# ADC_DSP.net
KiCad netlist of a schematic drawn in EAGLE
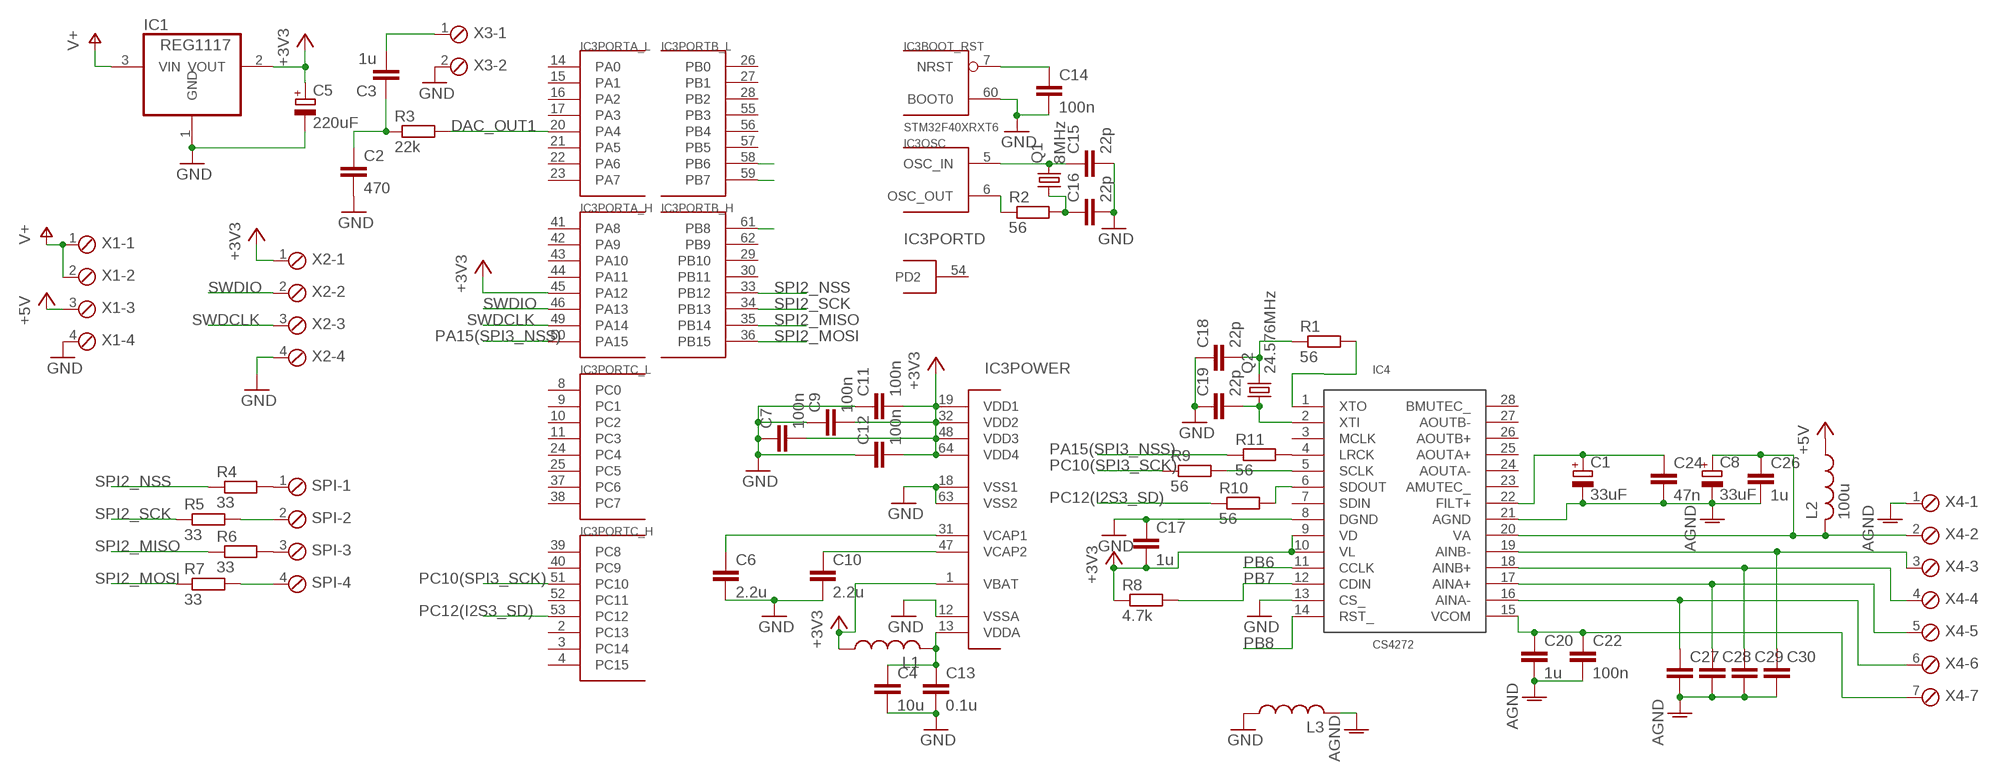
[diagram p0: schematic, sheet 1]

(export (version "E")
  (design (tool "Eeschema 10.0.6"))
  (components
    (comp (ref "C1")
      (value "33uF")
      (footprint "eagle-import:153CLV-0605")
      (libsource (lib "eagle-import") (part "CPOL-EU153CLV-0605"))
    )
    (comp (ref "C2")
      (value "470")
      (footprint "eagle-import:C0603")
      (libsource (lib "eagle-import") (part "C-EUC0603"))
    )
    (comp (ref "C3")
      (value "1u")
      (footprint "eagle-import:C0603")
      (libsource (lib "eagle-import") (part "C-EUC0603"))
    )
    (comp (ref "C4")
      (value "10u")
      (footprint "eagle-import:C0805")
      (libsource (lib "eagle-import") (part "C-EUC0805"))
    )
    (comp (ref "C5")
      (value "220uF")
      (footprint "eagle-import:153CLV-0605")
      (libsource (lib "eagle-import") (part "CPOL-EU153CLV-0605"))
    )
    (comp (ref "C6")
      (value "2.2u")
      (footprint "eagle-import:C0603")
      (libsource (lib "eagle-import") (part "C-EUC0603"))
    )
    (comp (ref "C7")
      (value "100n")
      (footprint "eagle-import:C0603")
      (libsource (lib "eagle-import") (part "C-EUC0603"))
    )
    (comp (ref "C8")
      (value "33uF")
      (footprint "eagle-import:153CLV-0605")
      (libsource (lib "eagle-import") (part "CPOL-EU153CLV-0605"))
    )
    (comp (ref "C9")
      (value "100n")
      (footprint "eagle-import:C0603")
      (libsource (lib "eagle-import") (part "C-EUC0603"))
    )
    (comp (ref "C10")
      (value "2.2u")
      (footprint "eagle-import:C0603")
      (libsource (lib "eagle-import") (part "C-EUC0603"))
    )
    (comp (ref "C11")
      (value "100n")
      (footprint "eagle-import:C0603")
      (libsource (lib "eagle-import") (part "C-EUC0603"))
    )
    (comp (ref "C12")
      (value "100n")
      (footprint "eagle-import:C0603")
      (libsource (lib "eagle-import") (part "C-EUC0603"))
    )
    (comp (ref "C13")
      (value "0.1u")
      (footprint "eagle-import:C0603")
      (libsource (lib "eagle-import") (part "C-EUC0603"))
    )
    (comp (ref "C14")
      (value "100n")
      (footprint "eagle-import:C0603")
      (libsource (lib "eagle-import") (part "C-EUC0603"))
    )
    (comp (ref "C15")
      (value "22p")
      (footprint "eagle-import:C0603")
      (libsource (lib "eagle-import") (part "C-EUC0603"))
    )
    (comp (ref "C16")
      (value "22p")
      (footprint "eagle-import:C0603")
      (libsource (lib "eagle-import") (part "C-EUC0603"))
    )
    (comp (ref "C17")
      (value "1u")
      (footprint "eagle-import:C0603")
      (libsource (lib "eagle-import") (part "C-EUC0603"))
    )
    (comp (ref "C18")
      (value "22p")
      (footprint "eagle-import:C0603")
      (libsource (lib "eagle-import") (part "C-EUC0603"))
    )
    (comp (ref "C19")
      (value "22p")
      (footprint "eagle-import:C0603")
      (libsource (lib "eagle-import") (part "C-EUC0603"))
    )
    (comp (ref "C20")
      (value "1u")
      (footprint "eagle-import:C0603")
      (libsource (lib "eagle-import") (part "C-EUC0603"))
    )
    (comp (ref "C22")
      (value "100n")
      (footprint "eagle-import:C0603")
      (libsource (lib "eagle-import") (part "C-EUC0603"))
    )
    (comp (ref "C24")
      (value "47n")
      (footprint "eagle-import:C0805")
      (libsource (lib "eagle-import") (part "C-EUC0805"))
    )
    (comp (ref "C26")
      (value "1u")
      (footprint "eagle-import:C0603")
      (libsource (lib "eagle-import") (part "C-EUC0603"))
    )
    (comp (ref "C27")
      (value "C-EUC0805")
      (footprint "eagle-import:C0805")
      (libsource (lib "eagle-import") (part "C-EUC0805"))
    )
    (comp (ref "C28")
      (value "C-EUC0805")
      (footprint "eagle-import:C0805")
      (libsource (lib "eagle-import") (part "C-EUC0805"))
    )
    (comp (ref "C29")
      (value "C-EUC0805")
      (footprint "eagle-import:C0805")
      (libsource (lib "eagle-import") (part "C-EUC0805"))
    )
    (comp (ref "C30")
      (value "C-EUC0805")
      (footprint "eagle-import:C0805")
      (libsource (lib "eagle-import") (part "C-EUC0805"))
    )
    (comp (ref "IC1")
      (value "REG1117")
      (footprint "eagle-import:SOT223")
      (libsource (lib "eagle-import") (part "REG1117"))
    )
    (comp (ref "IC3")
      (value "STM32F40XRXT6")
      (footprint "eagle-import:TQFP64")
      (libsource (lib "eagle-import") (part "STM32F40XRXT6"))
    )
    (comp (ref "IC4")
      (value "CS4272")
      (footprint "eagle-import:TSSOP28")
      (libsource (lib "eagle-import") (part "CS4272"))
    )
    (comp (ref "L1")
      (value "L-USL2012C")
      (footprint "eagle-import:L2012C")
      (libsource (lib "eagle-import") (part "L-USL2012C"))
    )
    (comp (ref "L2")
      (value "100u")
      (footprint "eagle-import:0207_12")
      (libsource (lib "eagle-import") (part "L-US0207/12"))
    )
    (comp (ref "L3")
      (value "L-USL2012C")
      (footprint "eagle-import:L2012C")
      (libsource (lib "eagle-import") (part "L-USL2012C"))
    )
    (comp (ref "Q1")
      (value "8MHz")
      (footprint "eagle-import:HC49_S")
      (libsource (lib "eagle-import") (part "CRYSTALHC49S"))
    )
    (comp (ref "Q2")
      (value "24.576MHz")
      (footprint "eagle-import:HC49_S")
      (libsource (lib "eagle-import") (part "CRYSTALHC49S"))
    )
    (comp (ref "R1")
      (value "56")
      (footprint "eagle-import:R0603")
      (libsource (lib "eagle-import") (part "R-EU_R0603"))
    )
    (comp (ref "R2")
      (value "56")
      (footprint "eagle-import:R0603")
      (libsource (lib "eagle-import") (part "R-EU_R0603"))
    )
    (comp (ref "R3")
      (value "22k")
      (footprint "eagle-import:R0603")
      (libsource (lib "eagle-import") (part "R-EU_R0603"))
    )
    (comp (ref "R4")
      (value "33")
      (footprint "eagle-import:R0603")
      (libsource (lib "eagle-import") (part "R-EU_R0603"))
    )
    (comp (ref "R5")
      (value "33")
      (footprint "eagle-import:R0603")
      (libsource (lib "eagle-import") (part "R-EU_R0603"))
    )
    (comp (ref "R6")
      (value "33")
      (footprint "eagle-import:R0603")
      (libsource (lib "eagle-import") (part "R-EU_R0603"))
    )
    (comp (ref "R7")
      (value "33")
      (footprint "eagle-import:R0603")
      (libsource (lib "eagle-import") (part "R-EU_R0603"))
    )
    (comp (ref "R8")
      (value "4.7k")
      (footprint "eagle-import:R0603")
      (libsource (lib "eagle-import") (part "R-EU_R0603"))
    )
    (comp (ref "R9")
      (value "56")
      (footprint "eagle-import:R0603")
      (libsource (lib "eagle-import") (part "R-EU_R0603"))
    )
    (comp (ref "R10")
      (value "56")
      (footprint "eagle-import:R0603")
      (libsource (lib "eagle-import") (part "R-EU_R0603"))
    )
    (comp (ref "R11")
      (value "56")
      (footprint "eagle-import:R0603")
      (libsource (lib "eagle-import") (part "R-EU_R0603"))
    )
    (comp (ref "SPI")
      (value "MPT4")
      (footprint "eagle-import:4POL254")
      (libsource (lib "eagle-import") (part "MPT4"))
    )
    (comp (ref "X1")
      (value "MPT4")
      (footprint "eagle-import:4POL254")
      (libsource (lib "eagle-import") (part "MPT4"))
    )
    (comp (ref "X2")
      (value "MPT4")
      (footprint "eagle-import:4POL254")
      (libsource (lib "eagle-import") (part "MPT4"))
    )
    (comp (ref "X3")
      (value "MPT2")
      (footprint "eagle-import:2POL254")
      (libsource (lib "eagle-import") (part "MPT2"))
    )
    (comp (ref "X4")
      (value "MPT7")
      (footprint "eagle-import:7POL254")
      (libsource (lib "eagle-import") (part "MPT7"))
    )
  )
  (nets
    (net (code "1") (name "+3V3") (class "Default")
      (node (ref "C11") (pin "2") (pinfunction "2_2") (pintype "passive"))
      (node (ref "C12") (pin "2") (pinfunction "2_2") (pintype "passive"))
      (node (ref "C17") (pin "2") (pinfunction "2_2") (pintype "passive"))
      (node (ref "C5") (pin "+") (pinfunction "+_+") (pintype "passive"))
      (node (ref "C7") (pin "2") (pinfunction "2_2") (pintype "passive"))
      (node (ref "C9") (pin "2") (pinfunction "2_2") (pintype "passive"))
      (node (ref "IC1") (pin "2") (pinfunction "VOUT_2") (pintype "output"))
      (node (ref "IC3") (pin "1") (pinfunction "VBAT_1") (pintype "bidirectional"))
      (node (ref "IC3") (pin "19") (pinfunction "VDD1_19") (pintype "bidirectional"))
      (node (ref "IC3") (pin "32") (pinfunction "VDD2_32") (pintype "bidirectional"))
      (node (ref "IC3") (pin "45") (pinfunction "PA12_45") (pintype "bidirectional"))
      (node (ref "IC3") (pin "48") (pinfunction "VDD3_48") (pintype "bidirectional"))
      (node (ref "IC3") (pin "64") (pinfunction "VDD4_64") (pintype "bidirectional"))
      (node (ref "IC4") (pin "10") (pinfunction "VL_10") (pintype "bidirectional"))
      (node (ref "IC4") (pin "9") (pinfunction "VD_9") (pintype "bidirectional"))
      (node (ref "L1") (pin "1") (pinfunction "1_1") (pintype "passive"))
      (node (ref "R8") (pin "1") (pinfunction "1_1") (pintype "passive"))
      (node (ref "X2") (pin "1") (pinfunction "1_1") (pintype "passive"))
    )
    (net (code "2") (name "+5V") (class "Default")
      (node (ref "L2") (pin "1") (pinfunction "1_1") (pintype "passive"))
      (node (ref "X1") (pin "3") (pinfunction "1_3") (pintype "passive"))
    )
    (net (code "3") (name "/DAC_OUT1") (class "Default")
      (node (ref "IC3") (pin "20") (pinfunction "PA4_20") (pintype "bidirectional"))
      (node (ref "R3") (pin "2") (pinfunction "2_2") (pintype "passive"))
    )
    (net (code "4") (name "/PA15(SPI3_NSS)") (class "Default")
      (node (ref "IC3") (pin "50") (pinfunction "PA15_50") (pintype "bidirectional"))
      (node (ref "R11") (pin "1") (pinfunction "1_1") (pintype "passive"))
    )
    (net (code "5") (name "/PB6") (class "Default")
      (node (ref "IC3") (pin "58") (pinfunction "PB6_58") (pintype "bidirectional"))
      (node (ref "IC4") (pin "11") (pinfunction "CCLK_11") (pintype "bidirectional"))
    )
    (net (code "6") (name "/PB7") (class "Default")
      (node (ref "IC3") (pin "59") (pinfunction "PB7_59") (pintype "bidirectional"))
      (node (ref "IC4") (pin "12") (pinfunction "CDIN_12") (pintype "bidirectional"))
      (node (ref "R8") (pin "2") (pinfunction "2_2") (pintype "passive"))
    )
    (net (code "7") (name "/PB8") (class "Default")
      (node (ref "IC3") (pin "61") (pinfunction "PB8_61") (pintype "bidirectional"))
      (node (ref "IC4") (pin "14") (pinfunction "RST__14") (pintype "bidirectional"))
    )
    (net (code "8") (name "/PC10(SPI3_SCK)") (class "Default")
      (node (ref "IC3") (pin "51") (pinfunction "PC10_51") (pintype "bidirectional"))
      (node (ref "R9") (pin "1") (pinfunction "1_1") (pintype "passive"))
    )
    (net (code "9") (name "/PC12(I2S3_SD)") (class "Default")
      (node (ref "IC3") (pin "53") (pinfunction "PC12_53") (pintype "bidirectional"))
      (node (ref "R10") (pin "1") (pinfunction "1_1") (pintype "passive"))
    )
    (net (code "10") (name "/SPI2_MISO") (class "Default")
      (node (ref "IC3") (pin "35") (pinfunction "PB14_35") (pintype "bidirectional"))
      (node (ref "R6") (pin "1") (pinfunction "1_1") (pintype "passive"))
    )
    (net (code "11") (name "/SPI2_MOSI") (class "Default")
      (node (ref "IC3") (pin "36") (pinfunction "PB15_36") (pintype "bidirectional"))
      (node (ref "R7") (pin "1") (pinfunction "1_1") (pintype "passive"))
    )
    (net (code "12") (name "/SPI2_NSS") (class "Default")
      (node (ref "IC3") (pin "33") (pinfunction "PB12_33") (pintype "bidirectional"))
      (node (ref "R4") (pin "1") (pinfunction "1_1") (pintype "passive"))
    )
    (net (code "13") (name "/SPI2_SCK") (class "Default")
      (node (ref "IC3") (pin "34") (pinfunction "PB13_34") (pintype "bidirectional"))
      (node (ref "R5") (pin "1") (pinfunction "1_1") (pintype "passive"))
    )
    (net (code "14") (name "/SWDCLK") (class "Default")
      (node (ref "IC3") (pin "49") (pinfunction "PA14_49") (pintype "bidirectional"))
      (node (ref "X2") (pin "3") (pinfunction "1_3") (pintype "passive"))
    )
    (net (code "15") (name "/SWDIO") (class "Default")
      (node (ref "IC3") (pin "46") (pinfunction "PA13_46") (pintype "bidirectional"))
      (node (ref "X2") (pin "2") (pinfunction "1_2") (pintype "passive"))
    )
    (net (code "16") (name "AGND") (class "Default")
      (node (ref "C1") (pin "-") (pinfunction "-_-") (pintype "passive"))
      (node (ref "C20") (pin "2") (pinfunction "2_2") (pintype "passive"))
      (node (ref "C22") (pin "2") (pinfunction "2_2") (pintype "passive"))
      (node (ref "C24") (pin "2") (pinfunction "2_2") (pintype "passive"))
      (node (ref "C26") (pin "2") (pinfunction "2_2") (pintype "passive"))
      (node (ref "C27") (pin "2") (pinfunction "2_2") (pintype "passive"))
      (node (ref "C28") (pin "2") (pinfunction "2_2") (pintype "passive"))
      (node (ref "C29") (pin "2") (pinfunction "2_2") (pintype "passive"))
      (node (ref "C30") (pin "2") (pinfunction "2_2") (pintype "passive"))
      (node (ref "C8") (pin "-") (pinfunction "-_-") (pintype "passive"))
      (node (ref "IC4") (pin "21") (pinfunction "AGND_21") (pintype "bidirectional"))
      (node (ref "L3") (pin "2") (pinfunction "2_2") (pintype "passive"))
      (node (ref "X4") (pin "1") (pinfunction "1_1") (pintype "passive"))
    )
    (net (code "17") (name "GND") (class "Default")
      (node (ref "C10") (pin "2") (pinfunction "2_2") (pintype "passive"))
      (node (ref "C11") (pin "1") (pinfunction "1_1") (pintype "passive"))
      (node (ref "C12") (pin "1") (pinfunction "1_1") (pintype "passive"))
      (node (ref "C13") (pin "2") (pinfunction "2_2") (pintype "passive"))
      (node (ref "C14") (pin "2") (pinfunction "2_2") (pintype "passive"))
      (node (ref "C15") (pin "2") (pinfunction "2_2") (pintype "passive"))
      (node (ref "C16") (pin "2") (pinfunction "2_2") (pintype "passive"))
      (node (ref "C17") (pin "1") (pinfunction "1_1") (pintype "passive"))
      (node (ref "C18") (pin "1") (pinfunction "1_1") (pintype "passive"))
      (node (ref "C19") (pin "1") (pinfunction "1_1") (pintype "passive"))
      (node (ref "C2") (pin "2") (pinfunction "2_2") (pintype "passive"))
      (node (ref "C4") (pin "2") (pinfunction "2_2") (pintype "passive"))
      (node (ref "C5") (pin "-") (pinfunction "-_-") (pintype "passive"))
      (node (ref "C6") (pin "2") (pinfunction "2_2") (pintype "passive"))
      (node (ref "C7") (pin "1") (pinfunction "1_1") (pintype "passive"))
      (node (ref "C9") (pin "1") (pinfunction "1_1") (pintype "passive"))
      (node (ref "IC1") (pin "1") (pinfunction "GND_1") (pintype "power_in"))
      (node (ref "IC3") (pin "12") (pinfunction "VSSA_12") (pintype "bidirectional"))
      (node (ref "IC3") (pin "18") (pinfunction "VSS1_18") (pintype "bidirectional"))
      (node (ref "IC3") (pin "60") (pinfunction "BOOT0_60") (pintype "input"))
      (node (ref "IC3") (pin "63") (pinfunction "VSS2_63") (pintype "bidirectional"))
      (node (ref "IC4") (pin "13") (pinfunction "CS__13") (pintype "bidirectional"))
      (node (ref "IC4") (pin "8") (pinfunction "DGND_8") (pintype "bidirectional"))
      (node (ref "L3") (pin "1") (pinfunction "1_1") (pintype "passive"))
      (node (ref "X1") (pin "4") (pinfunction "1_4") (pintype "passive"))
      (node (ref "X2") (pin "4") (pinfunction "1_4") (pintype "passive"))
      (node (ref "X3") (pin "2") (pinfunction "1_2") (pintype "passive"))
    )
    (net (code "18") (name "Net-(C2-Pad1)") (class "Default")
      (node (ref "C2") (pin "1") (pinfunction "1_1") (pintype "passive"))
      (node (ref "C3") (pin "1") (pinfunction "1_1") (pintype "passive"))
      (node (ref "R3") (pin "1") (pinfunction "1_1") (pintype "passive"))
    )
    (net (code "19") (name "Net-(C3-Pad2)") (class "Default")
      (node (ref "C3") (pin "2") (pinfunction "2_2") (pintype "passive"))
      (node (ref "X3") (pin "1") (pinfunction "1_1") (pintype "passive"))
    )
    (net (code "20") (name "Net-(C16-Pad1)") (class "Default")
      (node (ref "C16") (pin "1") (pinfunction "1_1") (pintype "passive"))
      (node (ref "Q1") (pin "1") (pinfunction "1_1") (pintype "passive"))
      (node (ref "R2") (pin "2") (pinfunction "2_2") (pintype "passive"))
    )
    (net (code "21") (name "Net-(C18-Pad2)") (class "Default")
      (node (ref "C18") (pin "2") (pinfunction "2_2") (pintype "passive"))
      (node (ref "Q2") (pin "2") (pinfunction "2_2") (pintype "passive"))
      (node (ref "R1") (pin "1") (pinfunction "1_1") (pintype "passive"))
    )
    (net (code "22") (name "Net-(IC3A-NRST)") (class "Default")
      (node (ref "C14") (pin "1") (pinfunction "1_1") (pintype "passive"))
      (node (ref "IC3") (pin "7") (pinfunction "NRST_7") (pintype "input"))
    )
    (net (code "23") (name "Net-(IC3B-OSC_IN)") (class "Default")
      (node (ref "C15") (pin "1") (pinfunction "1_1") (pintype "passive"))
      (node (ref "IC3") (pin "5") (pinfunction "OSC_IN_5") (pintype "input"))
      (node (ref "Q1") (pin "2") (pinfunction "2_2") (pintype "passive"))
    )
    (net (code "24") (name "Net-(IC3B-OSC_OUT)") (class "Default")
      (node (ref "IC3") (pin "6") (pinfunction "OSC_OUT_6") (pintype "output"))
      (node (ref "R2") (pin "1") (pinfunction "1_1") (pintype "passive"))
    )
    (net (code "25") (name "Net-(IC3J-VCAP1)") (class "Default")
      (node (ref "C6") (pin "1") (pinfunction "1_1") (pintype "passive"))
      (node (ref "IC3") (pin "31") (pinfunction "VCAP1_31") (pintype "bidirectional"))
    )
    (net (code "26") (name "Net-(IC3J-VCAP2)") (class "Default")
      (node (ref "C10") (pin "1") (pinfunction "1_1") (pintype "passive"))
      (node (ref "IC3") (pin "47") (pinfunction "VCAP2_47") (pintype "bidirectional"))
    )
    (net (code "27") (name "Net-(IC3J-VDDA)") (class "Default")
      (node (ref "C13") (pin "1") (pinfunction "1_1") (pintype "passive"))
      (node (ref "C4") (pin "1") (pinfunction "1_1") (pintype "passive"))
      (node (ref "IC3") (pin "13") (pinfunction "VDDA_13") (pintype "bidirectional"))
      (node (ref "L1") (pin "2") (pinfunction "2_2") (pintype "passive"))
    )
    (net (code "28") (name "Net-(IC4-AINA+)") (class "Default")
      (node (ref "C28") (pin "1") (pinfunction "1_1") (pintype "passive"))
      (node (ref "IC4") (pin "17") (pinfunction "AINA+_17") (pintype "bidirectional"))
      (node (ref "X4") (pin "5") (pinfunction "1_5") (pintype "passive"))
    )
    (net (code "29") (name "Net-(IC4-AINA-)") (class "Default")
      (node (ref "C27") (pin "1") (pinfunction "1_1") (pintype "passive"))
      (node (ref "IC4") (pin "16") (pinfunction "AINA-_16") (pintype "bidirectional"))
      (node (ref "X4") (pin "6") (pinfunction "1_6") (pintype "passive"))
    )
    (net (code "30") (name "Net-(IC4-AINB+)") (class "Default")
      (node (ref "C29") (pin "1") (pinfunction "1_1") (pintype "passive"))
      (node (ref "IC4") (pin "18") (pinfunction "AINB+_18") (pintype "bidirectional"))
      (node (ref "X4") (pin "4") (pinfunction "1_4") (pintype "passive"))
    )
    (net (code "31") (name "Net-(IC4-AINB-)") (class "Default")
      (node (ref "C30") (pin "1") (pinfunction "1_1") (pintype "passive"))
      (node (ref "IC4") (pin "19") (pinfunction "AINB-_19") (pintype "bidirectional"))
      (node (ref "X4") (pin "3") (pinfunction "1_3") (pintype "passive"))
    )
    (net (code "32") (name "Net-(IC4-FILT+)") (class "Default")
      (node (ref "C1") (pin "+") (pinfunction "+_+") (pintype "passive"))
      (node (ref "C24") (pin "1") (pinfunction "1_1") (pintype "passive"))
      (node (ref "IC4") (pin "22") (pinfunction "FILT+_22") (pintype "bidirectional"))
    )
    (net (code "33") (name "Net-(IC4-LRCK)") (class "Default")
      (node (ref "IC4") (pin "4") (pinfunction "LRCK_4") (pintype "bidirectional"))
      (node (ref "R11") (pin "2") (pinfunction "2_2") (pintype "passive"))
    )
    (net (code "34") (name "Net-(IC4-SCLK)") (class "Default")
      (node (ref "IC4") (pin "5") (pinfunction "SCLK_5") (pintype "bidirectional"))
      (node (ref "R9") (pin "2") (pinfunction "2_2") (pintype "passive"))
    )
    (net (code "35") (name "Net-(IC4-SDOUT)") (class "Default")
      (node (ref "IC4") (pin "6") (pinfunction "SDOUT_6") (pintype "bidirectional"))
      (node (ref "R10") (pin "2") (pinfunction "2_2") (pintype "passive"))
    )
    (net (code "36") (name "Net-(IC4-VA)") (class "Default")
      (node (ref "C26") (pin "1") (pinfunction "1_1") (pintype "passive"))
      (node (ref "C8") (pin "+") (pinfunction "+_+") (pintype "passive"))
      (node (ref "IC4") (pin "20") (pinfunction "VA_20") (pintype "bidirectional"))
      (node (ref "L2") (pin "2") (pinfunction "2_2") (pintype "passive"))
      (node (ref "X4") (pin "2") (pinfunction "1_2") (pintype "passive"))
    )
    (net (code "37") (name "Net-(IC4-VCOM)") (class "Default")
      (node (ref "C20") (pin "1") (pinfunction "1_1") (pintype "passive"))
      (node (ref "C22") (pin "1") (pinfunction "1_1") (pintype "passive"))
      (node (ref "IC4") (pin "15") (pinfunction "VCOM_15") (pintype "bidirectional"))
      (node (ref "X4") (pin "7") (pinfunction "1_7") (pintype "passive"))
    )
    (net (code "38") (name "Net-(IC4-XTI)") (class "Default")
      (node (ref "C19") (pin "2") (pinfunction "2_2") (pintype "passive"))
      (node (ref "IC4") (pin "2") (pinfunction "XTI_2") (pintype "bidirectional"))
      (node (ref "Q2") (pin "1") (pinfunction "1_1") (pintype "passive"))
    )
    (net (code "39") (name "Net-(IC4-XTO)") (class "Default")
      (node (ref "IC4") (pin "1") (pinfunction "XTO_1") (pintype "bidirectional"))
      (node (ref "R1") (pin "2") (pinfunction "2_2") (pintype "passive"))
    )
    (net (code "40") (name "Net-(R4-Pad2)") (class "Default")
      (node (ref "R4") (pin "2") (pinfunction "2_2") (pintype "passive"))
      (node (ref "SPI") (pin "1") (pinfunction "1_1") (pintype "passive"))
    )
    (net (code "41") (name "Net-(SPIB-1)") (class "Default")
      (node (ref "R5") (pin "2") (pinfunction "2_2") (pintype "passive"))
      (node (ref "SPI") (pin "2") (pinfunction "1_2") (pintype "passive"))
    )
    (net (code "42") (name "Net-(SPIC-1)") (class "Default")
      (node (ref "R6") (pin "2") (pinfunction "2_2") (pintype "passive"))
      (node (ref "SPI") (pin "3") (pinfunction "1_3") (pintype "passive"))
    )
    (net (code "43") (name "Net-(SPID-1)") (class "Default")
      (node (ref "R7") (pin "2") (pinfunction "2_2") (pintype "passive"))
      (node (ref "SPI") (pin "4") (pinfunction "1_4") (pintype "passive"))
    )
    (net (code "44") (name "V+") (class "Default")
      (node (ref "IC1") (pin "3") (pinfunction "VIN_3") (pintype "input"))
      (node (ref "X1") (pin "1") (pinfunction "1_1") (pintype "passive"))
      (node (ref "X1") (pin "2") (pinfunction "1_2") (pintype "passive"))
    )
    (net (code "45") (name "unconnected-(IC3C-PA8-Pad41)") (class "Default")
      (node (ref "IC3") (pin "41") (pinfunction "PA8_41") (pintype "bidirectional"))
    )
    (net (code "46") (name "unconnected-(IC3C-PA9-Pad42)") (class "Default")
      (node (ref "IC3") (pin "42") (pinfunction "PA9_42") (pintype "bidirectional"))
    )
    (net (code "47") (name "unconnected-(IC3C-PA10-Pad43)") (class "Default")
      (node (ref "IC3") (pin "43") (pinfunction "PA10_43") (pintype "bidirectional"))
    )
    (net (code "48") (name "unconnected-(IC3C-PA11-Pad44)") (class "Default")
      (node (ref "IC3") (pin "44") (pinfunction "PA11_44") (pintype "bidirectional"))
    )
    (net (code "49") (name "unconnected-(IC3D-PA0-Pad14)") (class "Default")
      (node (ref "IC3") (pin "14") (pinfunction "PA0_14") (pintype "bidirectional"))
    )
    (net (code "50") (name "unconnected-(IC3D-PA1-Pad15)") (class "Default")
      (node (ref "IC3") (pin "15") (pinfunction "PA1_15") (pintype "bidirectional"))
    )
    (net (code "51") (name "unconnected-(IC3D-PA2-Pad16)") (class "Default")
      (node (ref "IC3") (pin "16") (pinfunction "PA2_16") (pintype "bidirectional"))
    )
    (net (code "52") (name "unconnected-(IC3D-PA3-Pad17)") (class "Default")
      (node (ref "IC3") (pin "17") (pinfunction "PA3_17") (pintype "bidirectional"))
    )
    (net (code "53") (name "unconnected-(IC3D-PA5-Pad21)") (class "Default")
      (node (ref "IC3") (pin "21") (pinfunction "PA5_21") (pintype "bidirectional"))
    )
    (net (code "54") (name "unconnected-(IC3D-PA6-Pad22)") (class "Default")
      (node (ref "IC3") (pin "22") (pinfunction "PA6_22") (pintype "bidirectional"))
    )
    (net (code "55") (name "unconnected-(IC3D-PA7-Pad23)") (class "Default")
      (node (ref "IC3") (pin "23") (pinfunction "PA7_23") (pintype "bidirectional"))
    )
    (net (code "56") (name "unconnected-(IC3E-PB9-Pad62)") (class "Default")
      (node (ref "IC3") (pin "62") (pinfunction "PB9_62") (pintype "bidirectional"))
    )
    (net (code "57") (name "unconnected-(IC3E-PB10-Pad29)") (class "Default")
      (node (ref "IC3") (pin "29") (pinfunction "PB10_29") (pintype "bidirectional"))
    )
    (net (code "58") (name "unconnected-(IC3E-PB11-Pad30)") (class "Default")
      (node (ref "IC3") (pin "30") (pinfunction "PB11_30") (pintype "bidirectional"))
    )
    (net (code "59") (name "unconnected-(IC3F-PB0-Pad26)") (class "Default")
      (node (ref "IC3") (pin "26") (pinfunction "PB0_26") (pintype "bidirectional"))
    )
    (net (code "60") (name "unconnected-(IC3F-PB1-Pad27)") (class "Default")
      (node (ref "IC3") (pin "27") (pinfunction "PB1_27") (pintype "bidirectional"))
    )
    (net (code "61") (name "unconnected-(IC3F-PB2-Pad28)") (class "Default")
      (node (ref "IC3") (pin "28") (pinfunction "PB2_28") (pintype "bidirectional"))
    )
    (net (code "62") (name "unconnected-(IC3F-PB3-Pad55)") (class "Default")
      (node (ref "IC3") (pin "55") (pinfunction "PB3_55") (pintype "bidirectional"))
    )
    (net (code "63") (name "unconnected-(IC3F-PB4-Pad56)") (class "Default")
      (node (ref "IC3") (pin "56") (pinfunction "PB4_56") (pintype "bidirectional"))
    )
    (net (code "64") (name "unconnected-(IC3F-PB5-Pad57)") (class "Default")
      (node (ref "IC3") (pin "57") (pinfunction "PB5_57") (pintype "bidirectional"))
    )
    (net (code "65") (name "unconnected-(IC3G-PC8-Pad39)") (class "Default")
      (node (ref "IC3") (pin "39") (pinfunction "PC8_39") (pintype "bidirectional"))
    )
    (net (code "66") (name "unconnected-(IC3G-PC9-Pad40)") (class "Default")
      (node (ref "IC3") (pin "40") (pinfunction "PC9_40") (pintype "bidirectional"))
    )
    (net (code "67") (name "unconnected-(IC3G-PC11-Pad52)") (class "Default")
      (node (ref "IC3") (pin "52") (pinfunction "PC11_52") (pintype "bidirectional"))
    )
    (net (code "68") (name "unconnected-(IC3G-PC13-Pad2)") (class "Default")
      (node (ref "IC3") (pin "2") (pinfunction "PC13_2") (pintype "bidirectional"))
    )
    (net (code "69") (name "unconnected-(IC3G-PC14-Pad3)") (class "Default")
      (node (ref "IC3") (pin "3") (pinfunction "PC14_3") (pintype "bidirectional"))
    )
    (net (code "70") (name "unconnected-(IC3G-PC15-Pad4)") (class "Default")
      (node (ref "IC3") (pin "4") (pinfunction "PC15_4") (pintype "bidirectional"))
    )
    (net (code "71") (name "unconnected-(IC3H-PC0-Pad8)") (class "Default")
      (node (ref "IC3") (pin "8") (pinfunction "PC0_8") (pintype "bidirectional"))
    )
    (net (code "72") (name "unconnected-(IC3H-PC1-Pad9)") (class "Default")
      (node (ref "IC3") (pin "9") (pinfunction "PC1_9") (pintype "bidirectional"))
    )
    (net (code "73") (name "unconnected-(IC3H-PC2-Pad10)") (class "Default")
      (node (ref "IC3") (pin "10") (pinfunction "PC2_10") (pintype "bidirectional"))
    )
    (net (code "74") (name "unconnected-(IC3H-PC3-Pad11)") (class "Default")
      (node (ref "IC3") (pin "11") (pinfunction "PC3_11") (pintype "bidirectional"))
    )
    (net (code "75") (name "unconnected-(IC3H-PC4-Pad24)") (class "Default")
      (node (ref "IC3") (pin "24") (pinfunction "PC4_24") (pintype "bidirectional"))
    )
    (net (code "76") (name "unconnected-(IC3H-PC5-Pad25)") (class "Default")
      (node (ref "IC3") (pin "25") (pinfunction "PC5_25") (pintype "bidirectional"))
    )
    (net (code "77") (name "unconnected-(IC3H-PC6-Pad37)") (class "Default")
      (node (ref "IC3") (pin "37") (pinfunction "PC6_37") (pintype "bidirectional"))
    )
    (net (code "78") (name "unconnected-(IC3H-PC7-Pad38)") (class "Default")
      (node (ref "IC3") (pin "38") (pinfunction "PC7_38") (pintype "bidirectional"))
    )
    (net (code "79") (name "unconnected-(IC3I-PD2-Pad54)") (class "Default")
      (node (ref "IC3") (pin "54") (pinfunction "PD2_54") (pintype "bidirectional"))
    )
    (net (code "80") (name "unconnected-(IC4-AMUTEC_-Pad23)") (class "Default")
      (node (ref "IC4") (pin "23") (pinfunction "AMUTEC__23") (pintype "bidirectional"))
    )
    (net (code "81") (name "unconnected-(IC4-AOUTA+-Pad25)") (class "Default")
      (node (ref "IC4") (pin "25") (pinfunction "AOUTA+_25") (pintype "bidirectional"))
    )
    (net (code "82") (name "unconnected-(IC4-AOUTA--Pad24)") (class "Default")
      (node (ref "IC4") (pin "24") (pinfunction "AOUTA-_24") (pintype "bidirectional"))
    )
    (net (code "83") (name "unconnected-(IC4-AOUTB+-Pad26)") (class "Default")
      (node (ref "IC4") (pin "26") (pinfunction "AOUTB+_26") (pintype "bidirectional"))
    )
    (net (code "84") (name "unconnected-(IC4-AOUTB--Pad27)") (class "Default")
      (node (ref "IC4") (pin "27") (pinfunction "AOUTB-_27") (pintype "bidirectional"))
    )
    (net (code "85") (name "unconnected-(IC4-BMUTEC_-Pad28)") (class "Default")
      (node (ref "IC4") (pin "28") (pinfunction "BMUTEC__28") (pintype "bidirectional"))
    )
    (net (code "86") (name "unconnected-(IC4-MCLK-Pad3)") (class "Default")
      (node (ref "IC4") (pin "3") (pinfunction "MCLK_3") (pintype "bidirectional"))
    )
    (net (code "87") (name "unconnected-(IC4-SDIN-Pad7)") (class "Default")
      (node (ref "IC4") (pin "7") (pinfunction "SDIN_7") (pintype "bidirectional"))
    )
  )
)
